# Mini-DIN6_Breakout.net
KiCad netlist of a schematic drawn in Altium Designer
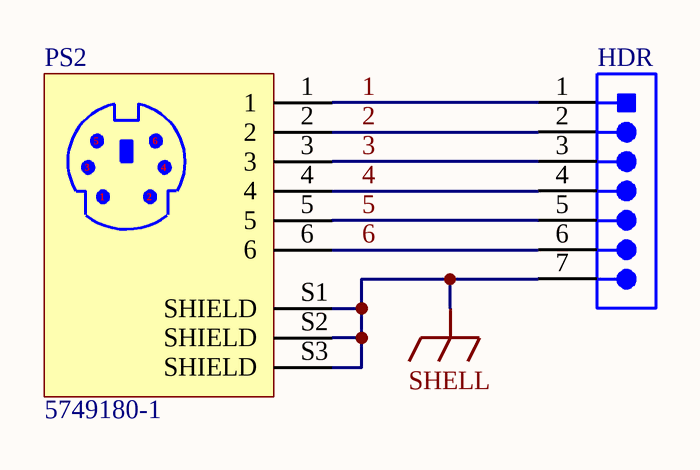
[diagram p0: Mini-DIN6 Breakout.SchDoc]

(export (version "E")
  (design (tool "Eeschema 10.0.6"))
  (components
    (comp (ref "HDR")
      (value "7 contacts Male header")
      (footprint "PH1-07-UA")
      (description "Connector Male Header 1X7 7contacts 0.100in pitch Gold Flash")
      (fields (field (name "MANUFACTURER") "Adam Tech"))
      (libsource (lib "Connectors") (part "Header 1X7"))
    )
    (comp (ref "PS2")
      (value "Mini DIN-6")
      (footprint "5749180-1")
      (description "6 Position Circular Connector Receptacle, Female Sockets Solder, Mini-DIN 6")
      (fields (field (name "MANUFACTURER") "Tyco Electronics") (field (name "MANUFACTURER P/N") "5749180-1"))
      (libsource (lib "Connectors") (part "5749180-1"))
    )
  )
  (nets
    (net (code "1") (name "/1") (class "Default")
      (node (ref "HDR") (pin "1") (pinfunction "1_1") (pintype "passive"))
      (node (ref "PS2") (pin "1") (pinfunction "1_1") (pintype "passive"))
    )
    (net (code "2") (name "/2") (class "Default")
      (node (ref "HDR") (pin "2") (pinfunction "2_2") (pintype "passive"))
      (node (ref "PS2") (pin "2") (pinfunction "2_2") (pintype "passive"))
    )
    (net (code "3") (name "/3") (class "Default")
      (node (ref "HDR") (pin "3") (pinfunction "3_3") (pintype "passive"))
      (node (ref "PS2") (pin "3") (pinfunction "3_3") (pintype "passive"))
    )
    (net (code "4") (name "/4") (class "Default")
      (node (ref "HDR") (pin "4") (pinfunction "4_4") (pintype "passive"))
      (node (ref "PS2") (pin "4") (pinfunction "4_4") (pintype "passive"))
    )
    (net (code "5") (name "/5") (class "Default")
      (node (ref "HDR") (pin "5") (pinfunction "5_5") (pintype "passive"))
      (node (ref "PS2") (pin "5") (pinfunction "5_5") (pintype "passive"))
    )
    (net (code "6") (name "/6") (class "Default")
      (node (ref "HDR") (pin "6") (pinfunction "6_6") (pintype "passive"))
      (node (ref "PS2") (pin "6") (pinfunction "6_6") (pintype "passive"))
    )
    (net (code "7") (name "SHELL") (class "Default")
      (node (ref "HDR") (pin "7") (pinfunction "7_7") (pintype "passive"))
      (node (ref "PS2") (pin "S1") (pinfunction "SHIELD_S1") (pintype "passive"))
      (node (ref "PS2") (pin "S2") (pinfunction "SHIELD_S2") (pintype "passive"))
      (node (ref "PS2") (pin "S3") (pinfunction "SHIELD_S3") (pintype "passive"))
    )
  )
)
